# 1.net
KiCad netlist of a schematic drawn in EasyEDA Pro
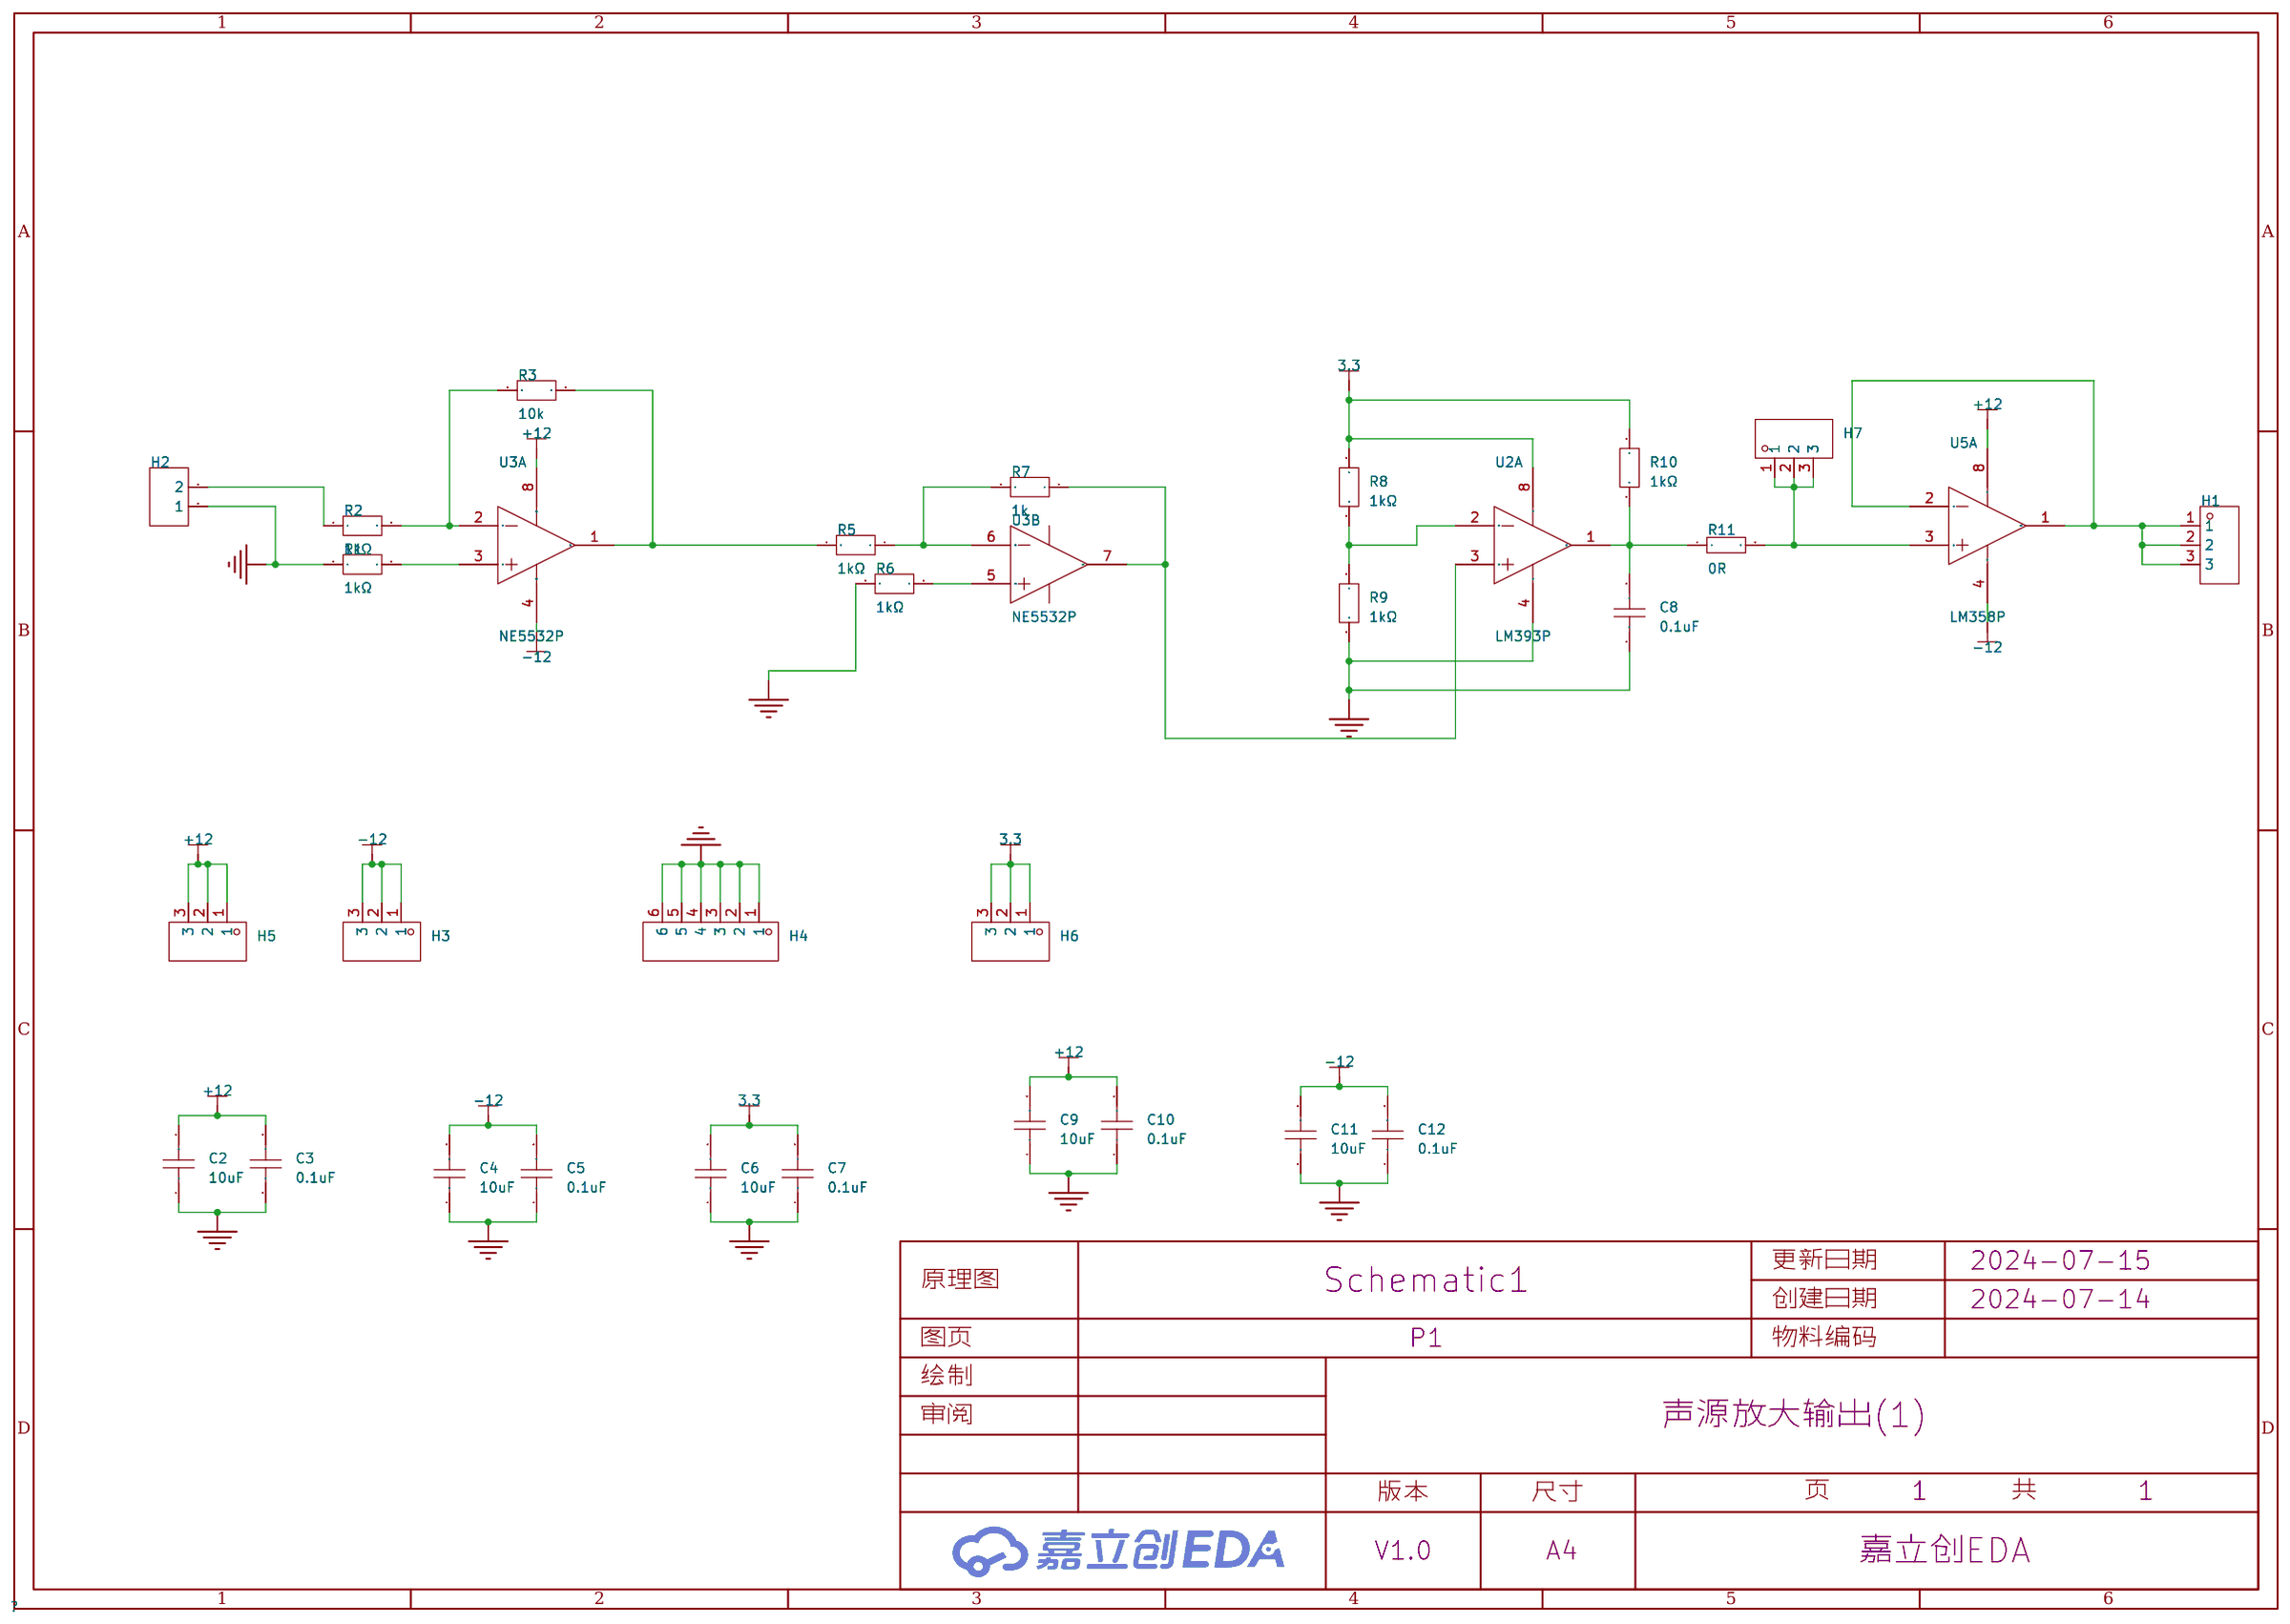
[diagram p0: schematic sheet]

(export (version "E")
  (design (tool "Eeschema 10.0.6"))
  (components
    (comp (ref "C2")
      (value "10uF")
      (footprint "easyedapro:CAP-TH_L4.2-W3.5-P2.54-D0.5")
      (description "容值:100nF;精度:±10%;额定电压:50V;温度系数:X7R;")
      (fields (field (name "Manufacturer Part") "178MU0006") (field (name "Manufacturer") "KNSCHA(科尼盛)"))
      (libsource (lib "easyedapro") (part "178MU0006"))
    )
    (comp (ref "C3")
      (value "0.1uF")
      (footprint "easyedapro:CAP-TH_L4.2-W3.5-P2.54-D0.5")
      (description "容值:100nF;精度:±10%;额定电压:50V;温度系数:X7R;")
      (fields (field (name "Manufacturer Part") "178MU0006") (field (name "Manufacturer") "KNSCHA(科尼盛)"))
      (libsource (lib "easyedapro") (part "178MU0006"))
    )
    (comp (ref "C4")
      (value "10uF")
      (footprint "easyedapro:CAP-TH_L4.2-W3.5-P2.54-D0.5")
      (description "容值:100nF;精度:±10%;额定电压:50V;温度系数:X7R;")
      (fields (field (name "Manufacturer Part") "178MU0006") (field (name "Manufacturer") "KNSCHA(科尼盛)"))
      (libsource (lib "easyedapro") (part "178MU0006"))
    )
    (comp (ref "C5")
      (value "0.1uF")
      (footprint "easyedapro:CAP-TH_L4.2-W3.5-P2.54-D0.5")
      (description "容值:100nF;精度:±10%;额定电压:50V;温度系数:X7R;")
      (fields (field (name "Manufacturer Part") "178MU0006") (field (name "Manufacturer") "KNSCHA(科尼盛)"))
      (libsource (lib "easyedapro") (part "178MU0006"))
    )
    (comp (ref "C6")
      (value "10uF")
      (footprint "easyedapro:CAP-TH_L4.2-W3.5-P2.54-D0.5")
      (description "容值:100nF;精度:±10%;额定电压:50V;温度系数:X7R;")
      (fields (field (name "Manufacturer Part") "178MU0006") (field (name "Manufacturer") "KNSCHA(科尼盛)"))
      (libsource (lib "easyedapro") (part "178MU0006"))
    )
    (comp (ref "C7")
      (value "0.1uF")
      (footprint "easyedapro:CAP-TH_L4.2-W3.5-P2.54-D0.5")
      (description "容值:100nF;精度:±10%;额定电压:50V;温度系数:X7R;")
      (fields (field (name "Manufacturer Part") "178MU0006") (field (name "Manufacturer") "KNSCHA(科尼盛)"))
      (libsource (lib "easyedapro") (part "178MU0006"))
    )
    (comp (ref "C8")
      (value "0.1uF")
      (footprint "easyedapro:CAP-TH_L4.2-W3.5-P2.54-D0.5")
      (description "容值:100nF;精度:±10%;额定电压:50V;温度系数:X7R;")
      (fields (field (name "Manufacturer Part") "178MU0006") (field (name "Manufacturer") "KNSCHA(科尼盛)"))
      (libsource (lib "easyedapro") (part "178MU0006"))
    )
    (comp (ref "C9")
      (value "10uF")
      (footprint "easyedapro:CAP-TH_L4.2-W3.5-P2.54-D0.5")
      (description "容值:100nF;精度:±10%;额定电压:50V;温度系数:X7R;")
      (fields (field (name "Manufacturer Part") "178MU0006") (field (name "Manufacturer") "KNSCHA(科尼盛)"))
      (libsource (lib "easyedapro") (part "178MU0006"))
    )
    (comp (ref "C10")
      (value "0.1uF")
      (footprint "easyedapro:CAP-TH_L4.2-W3.5-P2.54-D0.5")
      (description "容值:100nF;精度:±10%;额定电压:50V;温度系数:X7R;")
      (fields (field (name "Manufacturer Part") "178MU0006") (field (name "Manufacturer") "KNSCHA(科尼盛)"))
      (libsource (lib "easyedapro") (part "178MU0006"))
    )
    (comp (ref "C11")
      (value "10uF")
      (footprint "easyedapro:CAP-TH_L4.2-W3.5-P2.54-D0.5")
      (description "容值:100nF;精度:±10%;额定电压:50V;温度系数:X7R;")
      (fields (field (name "Manufacturer Part") "178MU0006") (field (name "Manufacturer") "KNSCHA(科尼盛)"))
      (libsource (lib "easyedapro") (part "178MU0006"))
    )
    (comp (ref "C12")
      (value "0.1uF")
      (footprint "easyedapro:CAP-TH_L4.2-W3.5-P2.54-D0.5")
      (description "容值:100nF;精度:±10%;额定电压:50V;温度系数:X7R;")
      (fields (field (name "Manufacturer Part") "178MU0006") (field (name "Manufacturer") "KNSCHA(科尼盛)"))
      (libsource (lib "easyedapro") (part "178MU0006"))
    )
    (comp (ref "H1")
      (value "~")
      (footprint "easyedapro:HDR-TH_3P-P2.54-V-F")
      (libsource (lib "easyedapro") (part "PM254V-11-03-H85"))
    )
    (comp (ref "H2")
      (value "~")
      (footprint "easyedapro:HDR-TH_2P-P2.54-V-F")
      (libsource (lib "easyedapro") (part "Header-Female-2.54_1x2"))
    )
    (comp (ref "H3")
      (value "~")
      (footprint "easyedapro:HDR-TH_3P-P2.54-V-F")
      (libsource (lib "easyedapro") (part "PM254V-11-03-H85"))
    )
    (comp (ref "H4")
      (value "~")
      (footprint "easyedapro:HDR-TH_6P-P2.54-V-F")
      (libsource (lib "easyedapro") (part "Header-Female-2.54_1x6"))
    )
    (comp (ref "H5")
      (value "~")
      (footprint "easyedapro:HDR-TH_3P-P2.54-V-F")
      (libsource (lib "easyedapro") (part "PM254V-11-03-H85"))
    )
    (comp (ref "H6")
      (value "~")
      (footprint "easyedapro:HDR-TH_3P-P2.54-V-F")
      (libsource (lib "easyedapro") (part "PM254V-11-03-H85"))
    )
    (comp (ref "H7")
      (value "~")
      (footprint "easyedapro:HDR-TH_3P-P2.54-V-F")
      (libsource (lib "easyedapro") (part "PM254V-11-03-H85"))
    )
    (comp (ref "R1")
      (value "1kΩ")
      (footprint "easyedapro:RES-TH_BD2.4-L6.3-P10.30-D0.6")
      (description "电阻类型:金属膜电阻;阻值:10kΩ;精度:±1%;功率:250mW;温度系数:±50ppm/°C;")
      (fields
        (field (name "Manufacturer Part") "RN1/4W10KFT/BA1")
        (field (name "Manufacturer") "Tyohm(幸亚电阻)")
      )
      (libsource (lib "easyedapro") (part "RN 1/4W 10K F T/B A1"))
    )
    (comp (ref "R2")
      (value "1kΩ")
      (footprint "easyedapro:RES-TH_BD2.4-L6.3-P10.30-D0.6")
      (description "电阻类型:金属膜电阻;阻值:10kΩ;精度:±1%;功率:250mW;温度系数:±50ppm/°C;")
      (fields
        (field (name "Manufacturer Part") "RN1/4W10KFT/BA1")
        (field (name "Manufacturer") "Tyohm(幸亚电阻)")
      )
      (libsource (lib "easyedapro") (part "RN 1/4W 10K F T/B A1"))
    )
    (comp (ref "R3")
      (value "10k")
      (footprint "easyedapro:RES-TH_BD2.4-L6.3-P10.30-D0.6")
      (description "电阻类型:金属膜电阻;阻值:10kΩ;精度:±1%;功率:250mW;温度系数:±50ppm/°C;")
      (fields
        (field (name "Manufacturer Part") "RN1/4W10KFT/BA1")
        (field (name "Manufacturer") "Tyohm(幸亚电阻)")
      )
      (libsource (lib "easyedapro") (part "RN 1/4W 10K F T/B A1"))
    )
    (comp (ref "R5")
      (value "1kΩ")
      (footprint "easyedapro:RES-TH_BD2.4-L6.3-P10.30-D0.6")
      (description "电阻类型:金属膜电阻;阻值:10kΩ;精度:±1%;功率:250mW;温度系数:±50ppm/°C;")
      (fields
        (field (name "Manufacturer Part") "RN1/4W10KFT/BA1")
        (field (name "Manufacturer") "Tyohm(幸亚电阻)")
      )
      (libsource (lib "easyedapro") (part "RN 1/4W 10K F T/B A1"))
    )
    (comp (ref "R6")
      (value "1kΩ")
      (footprint "easyedapro:RES-TH_BD2.4-L6.3-P10.30-D0.6")
      (description "电阻类型:金属膜电阻;阻值:10kΩ;精度:±1%;功率:250mW;温度系数:±50ppm/°C;")
      (fields
        (field (name "Manufacturer Part") "RN1/4W10KFT/BA1")
        (field (name "Manufacturer") "Tyohm(幸亚电阻)")
      )
      (libsource (lib "easyedapro") (part "RN 1/4W 10K F T/B A1"))
    )
    (comp (ref "R7")
      (value "1k")
      (footprint "easyedapro:RES-TH_BD2.4-L6.3-P10.30-D0.6")
      (description "电阻类型:金属膜电阻;阻值:10kΩ;精度:±1%;功率:250mW;温度系数:±50ppm/°C;")
      (fields
        (field (name "Manufacturer Part") "RN1/4W10KFT/BA1")
        (field (name "Manufacturer") "Tyohm(幸亚电阻)")
      )
      (libsource (lib "easyedapro") (part "RN 1/4W 10K F T/B A1"))
    )
    (comp (ref "R8")
      (value "1kΩ")
      (footprint "easyedapro:RES-TH_BD2.4-L6.3-P10.30-D0.6")
      (description "电阻类型:金属膜电阻;阻值:10kΩ;精度:±1%;功率:250mW;温度系数:±50ppm/°C;")
      (fields
        (field (name "Manufacturer Part") "RN1/4W10KFT/BA1")
        (field (name "Manufacturer") "Tyohm(幸亚电阻)")
      )
      (libsource (lib "easyedapro") (part "RN 1/4W 10K F T/B A1"))
    )
    (comp (ref "R9")
      (value "1kΩ")
      (footprint "easyedapro:RES-TH_BD2.4-L6.3-P10.30-D0.6")
      (description "电阻类型:金属膜电阻;阻值:10kΩ;精度:±1%;功率:250mW;温度系数:±50ppm/°C;")
      (fields
        (field (name "Manufacturer Part") "RN1/4W10KFT/BA1")
        (field (name "Manufacturer") "Tyohm(幸亚电阻)")
      )
      (libsource (lib "easyedapro") (part "RN 1/4W 10K F T/B A1"))
    )
    (comp (ref "R10")
      (value "1kΩ")
      (footprint "easyedapro:RES-TH_BD2.4-L6.3-P10.30-D0.6")
      (description "电阻类型:金属膜电阻;阻值:10kΩ;精度:±1%;功率:250mW;温度系数:±50ppm/°C;")
      (fields
        (field (name "Manufacturer Part") "RN1/4W10KFT/BA1")
        (field (name "Manufacturer") "Tyohm(幸亚电阻)")
      )
      (libsource (lib "easyedapro") (part "RN 1/4W 10K F T/B A1"))
    )
    (comp (ref "R11") (value "0R") (footprint "easyedapro:R0603") (libsource (lib "easyedapro") (part "电阻")))
    (comp (ref "U2")
      (value "LM393P")
      (footprint "easyedapro:DIP-8_L9.7-W6.4-P2.54-LS7.6-BL")
      (fields (field (name "Manufacturer") "Slkor(萨科微)"))
      (libsource (lib "easyedapro") (part "LM393P_C5355525"))
    )
    (comp (ref "U3")
      (value "NE5532P")
      (footprint "easyedapro:DIP-8_L9.4-W6.4-P2.54-LS9.1-BL")
      (description "放大器数:双路;增益带宽积(GBP):10MHz;输入偏置电流(Ib):200nA;压摆率(SR):9V/us;带宽(-3db):-;")
      (fields (field (name "Manufacturer") "TI(德州仪器)"))
      (libsource (lib "easyedapro") (part "NE5532P"))
    )
    (comp (ref "U5")
      (value "LM358P")
      (footprint "easyedapro:DIP-8_L9.7-W6.4-P2.54-LS7.6-BL")
      (fields (field (name "Manufacturer") "Slkor(萨科微)"))
      (libsource (lib "easyedapro") (part "LM358P_C5330384"))
    )
  )
  (nets
    (net (code "1") (name "+12") (class "Default")
      (node (ref "C10") (pin "2") (pinfunction "2_2") (pintype "unspecified"))
      (node (ref "C2") (pin "2") (pinfunction "2_2") (pintype "unspecified"))
      (node (ref "C3") (pin "2") (pinfunction "2_2") (pintype "unspecified"))
      (node (ref "C9") (pin "2") (pinfunction "2_2") (pintype "unspecified"))
      (node (ref "H5") (pin "1") (pinfunction "1_1") (pintype "unspecified"))
      (node (ref "H5") (pin "2") (pinfunction "2_2") (pintype "unspecified"))
      (node (ref "H5") (pin "3") (pinfunction "3_3") (pintype "unspecified"))
      (node (ref "U3") (pin "8") (pinfunction "VCC+_8") (pintype "unspecified"))
      (node (ref "U5") (pin "8") (pinfunction "VCC_8") (pintype "unspecified"))
    )
    (net (code "2") (name "-12") (class "Default")
      (node (ref "C11") (pin "2") (pinfunction "2_2") (pintype "unspecified"))
      (node (ref "C12") (pin "2") (pinfunction "2_2") (pintype "unspecified"))
      (node (ref "C4") (pin "2") (pinfunction "2_2") (pintype "unspecified"))
      (node (ref "C5") (pin "2") (pinfunction "2_2") (pintype "unspecified"))
      (node (ref "H3") (pin "1") (pinfunction "1_1") (pintype "unspecified"))
      (node (ref "H3") (pin "2") (pinfunction "2_2") (pintype "unspecified"))
      (node (ref "H3") (pin "3") (pinfunction "3_3") (pintype "unspecified"))
      (node (ref "U3") (pin "4") (pinfunction "VCC-_4") (pintype "unspecified"))
      (node (ref "U5") (pin "4") (pinfunction "GND_4") (pintype "unspecified"))
    )
    (net (code "3") (name "3.3") (class "Default")
      (node (ref "C6") (pin "2") (pinfunction "2_2") (pintype "unspecified"))
      (node (ref "C7") (pin "2") (pinfunction "2_2") (pintype "unspecified"))
      (node (ref "H6") (pin "1") (pinfunction "1_1") (pintype "unspecified"))
      (node (ref "H6") (pin "2") (pinfunction "2_2") (pintype "unspecified"))
      (node (ref "H6") (pin "3") (pinfunction "3_3") (pintype "unspecified"))
      (node (ref "R10") (pin "1") (pinfunction "1_1") (pintype "unspecified"))
      (node (ref "R8") (pin "1") (pinfunction "1_1") (pintype "unspecified"))
      (node (ref "U2") (pin "8") (pinfunction "VCC_8") (pintype "unspecified"))
    )
    (net (code "4") (name "GND") (class "Default")
      (node (ref "C10") (pin "1") (pinfunction "1_1") (pintype "unspecified"))
      (node (ref "C11") (pin "1") (pinfunction "1_1") (pintype "unspecified"))
      (node (ref "C12") (pin "1") (pinfunction "1_1") (pintype "unspecified"))
      (node (ref "C2") (pin "1") (pinfunction "1_1") (pintype "unspecified"))
      (node (ref "C3") (pin "1") (pinfunction "1_1") (pintype "unspecified"))
      (node (ref "C4") (pin "1") (pinfunction "1_1") (pintype "unspecified"))
      (node (ref "C5") (pin "1") (pinfunction "1_1") (pintype "unspecified"))
      (node (ref "C6") (pin "1") (pinfunction "1_1") (pintype "unspecified"))
      (node (ref "C7") (pin "1") (pinfunction "1_1") (pintype "unspecified"))
      (node (ref "C8") (pin "1") (pinfunction "1_1") (pintype "unspecified"))
      (node (ref "C9") (pin "1") (pinfunction "1_1") (pintype "unspecified"))
      (node (ref "H2") (pin "1") (pinfunction "1_1") (pintype "input"))
      (node (ref "H4") (pin "1") (pinfunction "1_1") (pintype "unspecified"))
      (node (ref "H4") (pin "2") (pinfunction "2_2") (pintype "unspecified"))
      (node (ref "H4") (pin "3") (pinfunction "3_3") (pintype "unspecified"))
      (node (ref "H4") (pin "4") (pinfunction "4_4") (pintype "unspecified"))
      (node (ref "H4") (pin "5") (pinfunction "5_5") (pintype "unspecified"))
      (node (ref "H4") (pin "6") (pinfunction "6_6") (pintype "unspecified"))
      (node (ref "R1") (pin "1") (pinfunction "1_1") (pintype "unspecified"))
      (node (ref "R6") (pin "2") (pinfunction "2_2") (pintype "unspecified"))
      (node (ref "R9") (pin "2") (pinfunction "2_2") (pintype "unspecified"))
      (node (ref "U2") (pin "4") (pinfunction "GND_4") (pintype "unspecified"))
    )
    (net (code "5") (name "Net-(H2-Pad2)") (class "Default")
      (node (ref "H2") (pin "2") (pinfunction "2_2") (pintype "input"))
      (node (ref "R2") (pin "1") (pinfunction "1_1") (pintype "unspecified"))
    )
    (net (code "6") (name "Net-(U2A-INA+)") (class "Default")
      (node (ref "R7") (pin "1") (pinfunction "1_1") (pintype "unspecified"))
      (node (ref "U2") (pin "3") (pinfunction "INA+_3") (pintype "unspecified"))
      (node (ref "U3") (pin "7") (pinfunction "OUT2_7") (pintype "output"))
    )
    (net (code "7") (name "Net-(U2A-INA-)") (class "Default")
      (node (ref "R8") (pin "2") (pinfunction "2_2") (pintype "unspecified"))
      (node (ref "R9") (pin "1") (pinfunction "1_1") (pintype "unspecified"))
      (node (ref "U2") (pin "2") (pinfunction "INA-_2") (pintype "unspecified"))
    )
    (net (code "8") (name "Net-(U2A-OUTA)") (class "Default")
      (node (ref "C8") (pin "2") (pinfunction "2_2") (pintype "unspecified"))
      (node (ref "R10") (pin "2") (pinfunction "2_2") (pintype "unspecified"))
      (node (ref "R11") (pin "1") (pinfunction "1_1") (pintype "input"))
      (node (ref "U2") (pin "1") (pinfunction "OUTA_1") (pintype "output"))
    )
    (net (code "9") (name "Net-(U3A-IN1+)") (class "Default")
      (node (ref "R1") (pin "2") (pinfunction "2_2") (pintype "unspecified"))
      (node (ref "U3") (pin "3") (pinfunction "IN1+_3") (pintype "unspecified"))
    )
    (net (code "10") (name "Net-(U3A-IN1-)") (class "Default")
      (node (ref "R2") (pin "2") (pinfunction "2_2") (pintype "unspecified"))
      (node (ref "R3") (pin "1") (pinfunction "1_1") (pintype "unspecified"))
      (node (ref "U3") (pin "2") (pinfunction "IN1-_2") (pintype "unspecified"))
    )
    (net (code "11") (name "Net-(U3A-OUT1)") (class "Default")
      (node (ref "R3") (pin "2") (pinfunction "2_2") (pintype "unspecified"))
      (node (ref "R5") (pin "2") (pinfunction "2_2") (pintype "unspecified"))
      (node (ref "U3") (pin "1") (pinfunction "OUT1_1") (pintype "output"))
    )
    (net (code "12") (name "Net-(U3B-IN2+)") (class "Default")
      (node (ref "R6") (pin "1") (pinfunction "1_1") (pintype "unspecified"))
      (node (ref "U3") (pin "5") (pinfunction "IN2+_5") (pintype "unspecified"))
    )
    (net (code "13") (name "Net-(U3B-IN2-)") (class "Default")
      (node (ref "R5") (pin "1") (pinfunction "1_1") (pintype "unspecified"))
      (node (ref "R7") (pin "2") (pinfunction "2_2") (pintype "unspecified"))
      (node (ref "U3") (pin "6") (pinfunction "IN2-_6") (pintype "unspecified"))
    )
    (net (code "14") (name "Net-(U5A-IN1+)") (class "Default")
      (node (ref "H7") (pin "1") (pinfunction "1_1") (pintype "unspecified"))
      (node (ref "H7") (pin "2") (pinfunction "2_2") (pintype "unspecified"))
      (node (ref "H7") (pin "3") (pinfunction "3_3") (pintype "unspecified"))
      (node (ref "R11") (pin "2") (pinfunction "2_2") (pintype "input"))
      (node (ref "U5") (pin "3") (pinfunction "IN1+_3") (pintype "unspecified"))
    )
    (net (code "15") (name "Net-(U5A-IN1-)") (class "Default")
      (node (ref "H1") (pin "1") (pinfunction "1_1") (pintype "unspecified"))
      (node (ref "H1") (pin "2") (pinfunction "2_2") (pintype "unspecified"))
      (node (ref "H1") (pin "3") (pinfunction "3_3") (pintype "unspecified"))
      (node (ref "U5") (pin "1") (pinfunction "OUT1_1") (pintype "output"))
      (node (ref "U5") (pin "2") (pinfunction "IN1-_2") (pintype "unspecified"))
    )
  )
)
